# DAC_ADC.net
KiCad netlist of a schematic drawn in Altium Designer
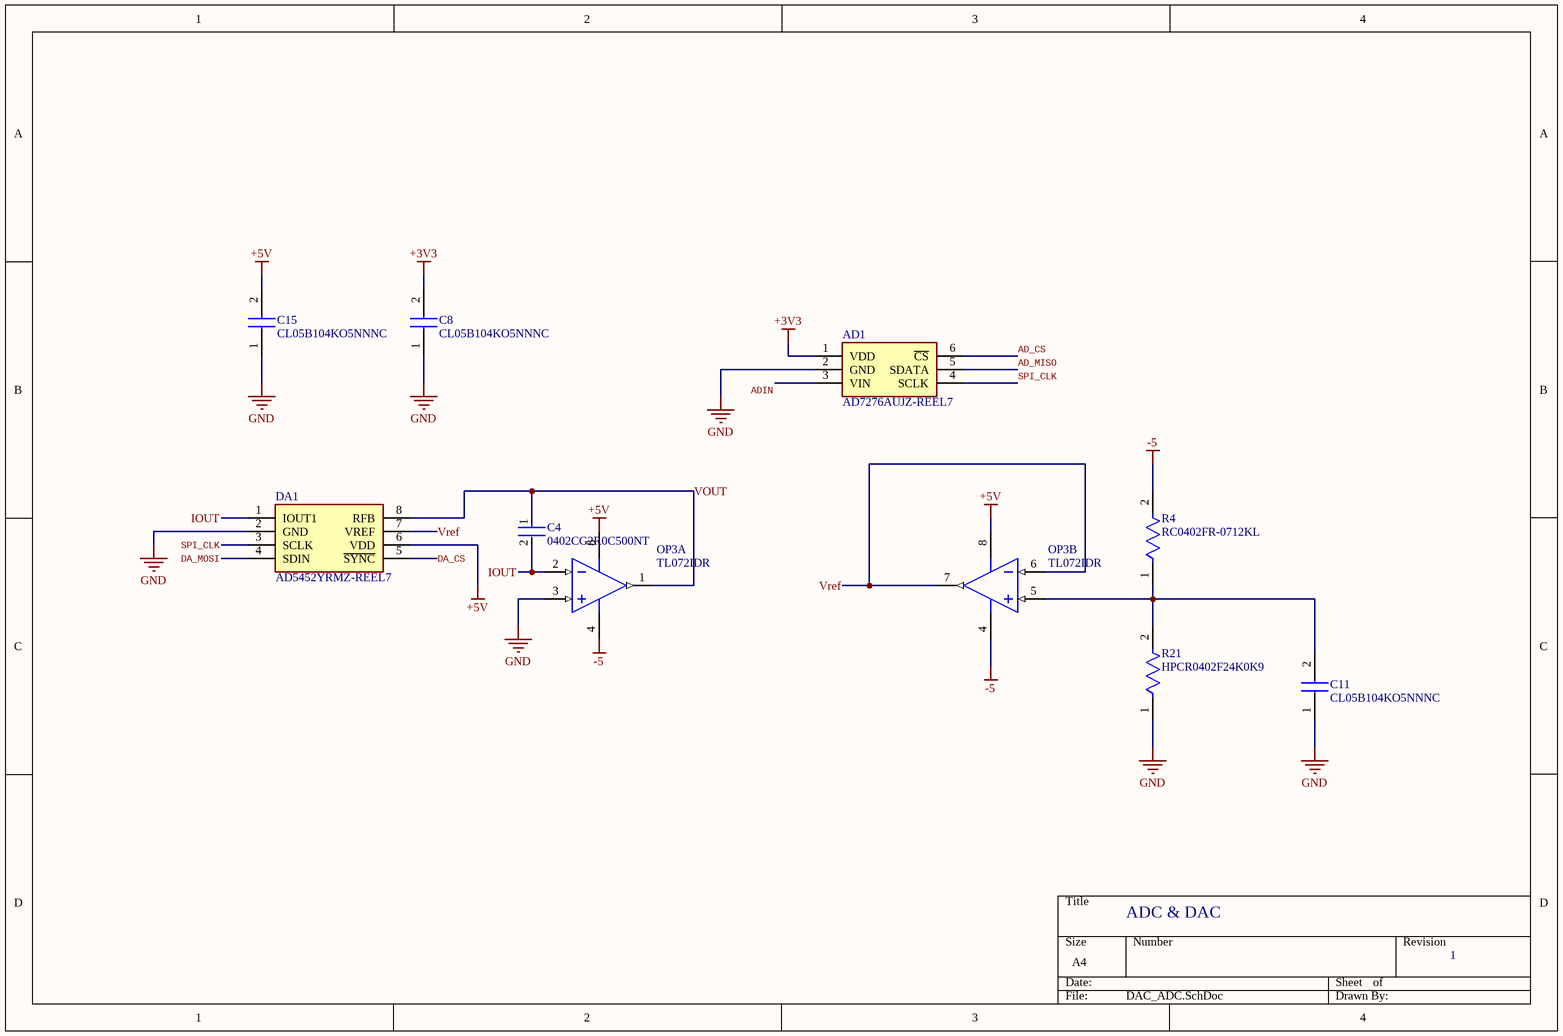
[diagram p0: DAC_ADC.SchDoc]

(export (version "E")
  (design (tool "Eeschema 10.0.6"))
  (components
    (comp (ref "AD1")
      (value "AD7276AUJZ-REEL7")
      (footprint "SamacSys:SOT95P280X100-6N")
      (description "Integrated Circuit")
      (fields (field (name "MOUSER PART NUMBER") "584-AD7276AUJZ-R7"))
      (libsource (lib "*") (part "AD7276AUJZ-REEL7"))
    )
    (comp (ref "C4")
      (value "0402CG2R0C500NT")
      (footprint "FP-GJM155-0_05-IPC_C")
      (description "Multi-Layer Ceramic Capacitor 2pF C0G  ±0.1pF 0402 Paper T/R")
      (libsource (lib "Altium Content Vault") (part "02cd4be3c70576c341d710602a673aa"))
    )
    (comp (ref "C8")
      (value "CL05B104KO5NNNC")
      (footprint "SamacSys:CAPC1005X55N")
      (description "Capacitor")
      (fields (field (name "MOUSER PART NUMBER") "187-CL05B104KO5NNNC"))
      (libsource (lib "*") (part "CL05B104KO5NNNC"))
    )
    (comp (ref "C11")
      (value "CL05B104KO5NNNC")
      (footprint "SamacSys:CAPC1005X55N")
      (description "Capacitor")
      (fields (field (name "MOUSER PART NUMBER") "187-CL05B104KO5NNNC"))
      (libsource (lib "*") (part "CL05B104KO5NNNC"))
    )
    (comp (ref "C15")
      (value "CL05B104KO5NNNC")
      (footprint "SamacSys:CAPC1005X55N")
      (description "Capacitor")
      (fields (field (name "MOUSER PART NUMBER") "187-CL05B104KO5NNNC"))
      (libsource (lib "E_tactile_components") (part "CL05B104KO5NNNC"))
    )
    (comp (ref "DA1")
      (value "AD5452YRMZ-REEL7")
      (footprint "SamacSys:SOP65P490X110-8N")
      (description "Integrated Circuit")
      (fields (field (name "MOUSER PART NUMBER") "584-AD5452YRMZ-R7"))
      (libsource (lib "*") (part "AD5452YRMZ-REEL7"))
    )
    (comp (ref "OP3")
      (value "TL072IDR")
      (footprint "D0008A_L")
      (fields (field (name "MANUFACTURER") "Texas Instruments"))
      (libsource (lib "Altium Content Vault") (part "TI-AMP-D6-2-8_D"))
    )
    (comp (ref "R4")
      (value "RC0402FR-0712KL")
      (footprint "FP-RC0402-0_4-IPC_C")
      (description "RES SMD 12K OHM 1% 1/16W 0402")
      (fields (field (name "TOLERANCE") "1%"))
      (libsource (lib "Altium Content Vault") (part "1029c3af85768c4190bb7ad29bc67b5"))
    )
    (comp (ref "R21")
      (value "HPCR0402F24K0K9")
      (footprint "FP-RT0402-MFG")
      (description "RES SMD 12K OHM 1% 1/16W 0402")
      (fields
        (field (name "TOLERANCE") "0.01")
        (field (name "OCTOPART") "https://octopart.com/rt0402fre0714kl-yageo-1378200")
      )
      (libsource (lib "Altium Content Vault") (part "1029c3af85768c4190bb7ad29bc67b5"))
    )
  )
  (nets
    (net (code "1") (name "+3V3") (class "Default")
      (node (ref "AD1") (pin "1") (pinfunction "VDD_1") (pintype "passive"))
      (node (ref "C8") (pin "2") (pinfunction "2_2") (pintype "passive"))
    )
    (net (code "2") (name "+5V") (class "Default")
      (node (ref "C15") (pin "2") (pinfunction "2_2") (pintype "passive"))
      (node (ref "DA1") (pin "6") (pinfunction "VDD_6") (pintype "passive"))
      (node (ref "OP3") (pin "8") (pinfunction "VCC+_8") (pintype "power_in"))
    )
    (net (code "3") (name "-5") (class "Default")
      (node (ref "OP3") (pin "4") (pinfunction "VCC-_4") (pintype "passive"))
      (node (ref "R4") (pin "2") (pinfunction "2_2") (pintype "passive"))
    )
    (net (code "4") (name "/ADIN") (class "Default")
      (node (ref "AD1") (pin "3") (pinfunction "VIN_3") (pintype "passive"))
    )
    (net (code "5") (name "/AD_CS") (class "Default")
      (node (ref "AD1") (pin "6") (pinfunction "~{CS}_6") (pintype "passive"))
    )
    (net (code "6") (name "/AD_MISO") (class "Default")
      (node (ref "AD1") (pin "5") (pinfunction "SDATA_5") (pintype "passive"))
    )
    (net (code "7") (name "/DA_CS") (class "Default")
      (node (ref "DA1") (pin "5") (pinfunction "~{SYNC}_5") (pintype "passive"))
    )
    (net (code "8") (name "/DA_MOSI") (class "Default")
      (node (ref "DA1") (pin "4") (pinfunction "SDIN_4") (pintype "passive"))
    )
    (net (code "9") (name "/IOUT") (class "Default")
      (node (ref "C4") (pin "2") (pinfunction "2_2") (pintype "passive"))
      (node (ref "DA1") (pin "1") (pinfunction "IOUT1_1") (pintype "passive"))
      (node (ref "OP3") (pin "2") (pinfunction "IN1-_2") (pintype "input"))
    )
    (net (code "10") (name "/SPI_CLK") (class "Default")
      (node (ref "AD1") (pin "4") (pinfunction "SCLK_4") (pintype "passive"))
      (node (ref "DA1") (pin "3") (pinfunction "SCLK_3") (pintype "passive"))
    )
    (net (code "11") (name "/VOUT") (class "Default")
      (node (ref "C4") (pin "1") (pinfunction "1_1") (pintype "passive"))
      (node (ref "DA1") (pin "8") (pinfunction "RFB_8") (pintype "passive"))
      (node (ref "OP3") (pin "1") (pinfunction "OUT1_1") (pintype "output"))
    )
    (net (code "12") (name "/Vref") (class "Default")
      (node (ref "DA1") (pin "7") (pinfunction "VREF_7") (pintype "passive"))
      (node (ref "OP3") (pin "6") (pinfunction "IN2-_6") (pintype "input"))
      (node (ref "OP3") (pin "7") (pinfunction "OUT2_7") (pintype "output"))
    )
    (net (code "13") (name "GND") (class "Default")
      (node (ref "AD1") (pin "2") (pinfunction "GND_2") (pintype "passive"))
      (node (ref "C11") (pin "1") (pinfunction "1_1") (pintype "passive"))
      (node (ref "C15") (pin "1") (pinfunction "1_1") (pintype "passive"))
      (node (ref "C8") (pin "1") (pinfunction "1_1") (pintype "passive"))
      (node (ref "DA1") (pin "2") (pinfunction "GND_2") (pintype "passive"))
      (node (ref "OP3") (pin "3") (pinfunction "IN1+_3") (pintype "input"))
      (node (ref "R21") (pin "1") (pinfunction "1_1") (pintype "passive"))
    )
    (net (code "14") (name "Net-(OP3B-IN2+)") (class "Default")
      (node (ref "C11") (pin "2") (pinfunction "2_2") (pintype "passive"))
      (node (ref "OP3") (pin "5") (pinfunction "IN2+_5") (pintype "input"))
      (node (ref "R21") (pin "2") (pinfunction "2_2") (pintype "passive"))
      (node (ref "R4") (pin "1") (pinfunction "1_1") (pintype "passive"))
    )
  )
)
